# squaresynth.net
KiCad netlist of a schematic drawn in EAGLE
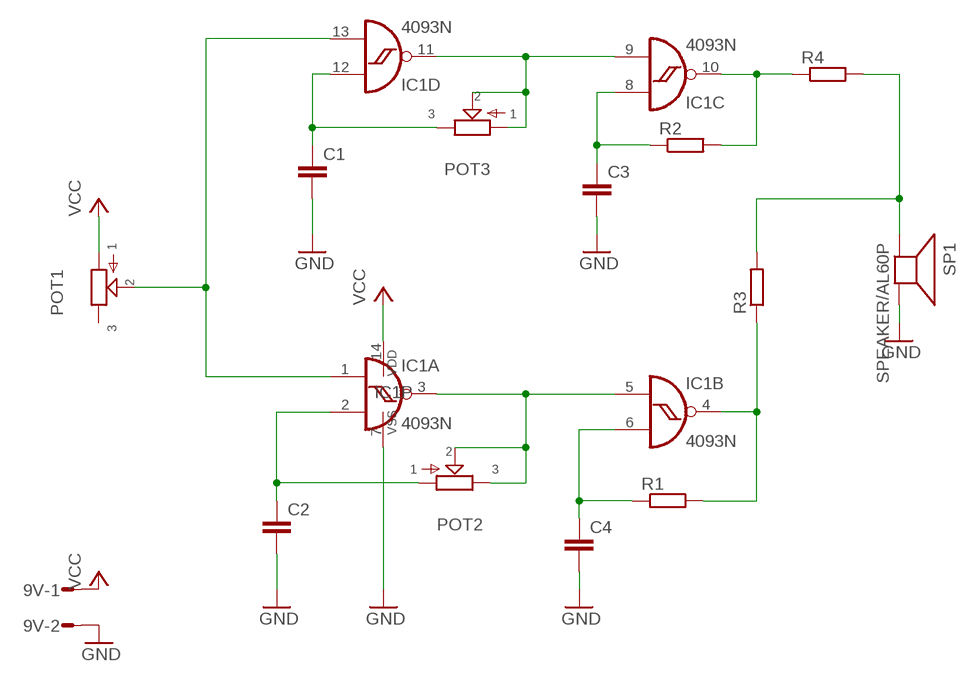
[diagram p0: schematic, sheet 1]

(export (version "E")
  (design (tool "Eeschema 10.0.6"))
  (components
    (comp (ref "9V")
      (value "M02S")
      (footprint "eagle-import:02P")
      (libsource (lib "eagle-import") (part "M02S"))
    )
    (comp (ref "C1")
      (value "C-EU050-030X075")
      (footprint "eagle-import:C050-030X075")
      (libsource (lib "eagle-import") (part "C-EU050-030X075"))
    )
    (comp (ref "C2")
      (value "C-EU050-030X075")
      (footprint "eagle-import:C050-030X075")
      (libsource (lib "eagle-import") (part "C-EU050-030X075"))
    )
    (comp (ref "C3")
      (value "C-EU075-032X103")
      (footprint "eagle-import:C075-032X103")
      (libsource (lib "eagle-import") (part "C-EU075-032X103"))
    )
    (comp (ref "C4")
      (value "C-EU075-032X103")
      (footprint "eagle-import:C075-032X103")
      (libsource (lib "eagle-import") (part "C-EU075-032X103"))
    )
    (comp (ref "IC1")
      (value "4093N")
      (footprint "eagle-import:DIL14")
      (libsource (lib "eagle-import") (part "4093N"))
    )
    (comp (ref "POT1")
      (value "POT-EU16MM")
      (footprint "eagle-import:16MM")
      (libsource (lib "eagle-import") (part "POT-EU16MM"))
    )
    (comp (ref "POT2")
      (value "POT-EU16MM")
      (footprint "eagle-import:16MM")
      (libsource (lib "eagle-import") (part "POT-EU16MM"))
    )
    (comp (ref "POT3")
      (value "POT-EU16MM")
      (footprint "eagle-import:16MM")
      (libsource (lib "eagle-import") (part "POT-EU16MM"))
    )
    (comp (ref "R1")
      (value "R-EU_0309/12")
      (footprint "eagle-import:0309_12")
      (libsource (lib "eagle-import") (part "R-EU_0309/12"))
    )
    (comp (ref "R2")
      (value "R-EU_0309/12")
      (footprint "eagle-import:0309_12")
      (libsource (lib "eagle-import") (part "R-EU_0309/12"))
    )
    (comp (ref "R3")
      (value "R-EU_0309/12")
      (footprint "eagle-import:0309_12")
      (libsource (lib "eagle-import") (part "R-EU_0309/12"))
    )
    (comp (ref "R4")
      (value "R-EU_0309/12")
      (footprint "eagle-import:0309_12")
      (libsource (lib "eagle-import") (part "R-EU_0309/12"))
    )
    (comp (ref "SP1")
      (value "SPEAKER/AL60P")
      (footprint "eagle-import:AL60P")
      (libsource (lib "eagle-import") (part "SPEAKER/AL60P"))
    )
  )
  (nets
    (net (code "1") (name "GND") (class "Default")
      (node (ref "9V") (pin "2") (pinfunction "S_2") (pintype "passive"))
      (node (ref "C1") (pin "2") (pinfunction "2_2") (pintype "passive"))
      (node (ref "C2") (pin "2") (pinfunction "2_2") (pintype "passive"))
      (node (ref "C3") (pin "2") (pinfunction "2_2") (pintype "passive"))
      (node (ref "C4") (pin "2") (pinfunction "2_2") (pintype "passive"))
      (node (ref "IC1") (pin "7") (pinfunction "VSS_7") (pintype "power_in"))
      (node (ref "SP1") (pin "2") (pinfunction "-_2") (pintype "passive"))
    )
    (net (code "2") (name "Net-(IC1A-I0)") (class "Default")
      (node (ref "IC1") (pin "1") (pinfunction "I0_1") (pintype "input"))
      (node (ref "IC1") (pin "13") (pinfunction "I1_13") (pintype "input"))
      (node (ref "POT1") (pin "2") (pinfunction "2_2") (pintype "passive"))
    )
    (net (code "3") (name "Net-(IC1A-I1)") (class "Default")
      (node (ref "C2") (pin "1") (pinfunction "1_1") (pintype "passive"))
      (node (ref "IC1") (pin "2") (pinfunction "I1_2") (pintype "input"))
      (node (ref "POT2") (pin "1") (pinfunction "1_1") (pintype "passive"))
    )
    (net (code "4") (name "Net-(IC1A-O)") (class "Default")
      (node (ref "IC1") (pin "3") (pinfunction "O_3") (pintype "output"))
      (node (ref "IC1") (pin "5") (pinfunction "I0_5") (pintype "input"))
      (node (ref "POT2") (pin "2") (pinfunction "2_2") (pintype "passive"))
      (node (ref "POT2") (pin "3") (pinfunction "3_3") (pintype "passive"))
    )
    (net (code "5") (name "Net-(IC1B-I1)") (class "Default")
      (node (ref "C4") (pin "1") (pinfunction "1_1") (pintype "passive"))
      (node (ref "IC1") (pin "6") (pinfunction "I1_6") (pintype "input"))
      (node (ref "R1") (pin "1") (pinfunction "1_1") (pintype "passive"))
    )
    (net (code "6") (name "Net-(IC1B-O)") (class "Default")
      (node (ref "IC1") (pin "4") (pinfunction "O_4") (pintype "output"))
      (node (ref "R1") (pin "2") (pinfunction "2_2") (pintype "passive"))
      (node (ref "R3") (pin "1") (pinfunction "1_1") (pintype "passive"))
    )
    (net (code "7") (name "Net-(IC1C-I0)") (class "Default")
      (node (ref "C3") (pin "1") (pinfunction "1_1") (pintype "passive"))
      (node (ref "IC1") (pin "8") (pinfunction "I0_8") (pintype "input"))
      (node (ref "R2") (pin "1") (pinfunction "1_1") (pintype "passive"))
    )
    (net (code "8") (name "Net-(IC1C-I1)") (class "Default")
      (node (ref "IC1") (pin "11") (pinfunction "O_11") (pintype "output"))
      (node (ref "IC1") (pin "9") (pinfunction "I1_9") (pintype "input"))
      (node (ref "POT3") (pin "1") (pinfunction "1_1") (pintype "passive"))
      (node (ref "POT3") (pin "2") (pinfunction "2_2") (pintype "passive"))
    )
    (net (code "9") (name "Net-(IC1C-O)") (class "Default")
      (node (ref "IC1") (pin "10") (pinfunction "O_10") (pintype "output"))
      (node (ref "R2") (pin "2") (pinfunction "2_2") (pintype "passive"))
      (node (ref "R4") (pin "1") (pinfunction "1_1") (pintype "passive"))
    )
    (net (code "10") (name "Net-(IC1D-I0)") (class "Default")
      (node (ref "C1") (pin "1") (pinfunction "1_1") (pintype "passive"))
      (node (ref "IC1") (pin "12") (pinfunction "I0_12") (pintype "input"))
      (node (ref "POT3") (pin "3") (pinfunction "3_3") (pintype "passive"))
    )
    (net (code "11") (name "Net-(SP1-+)") (class "Default")
      (node (ref "R3") (pin "2") (pinfunction "2_2") (pintype "passive"))
      (node (ref "R4") (pin "2") (pinfunction "2_2") (pintype "passive"))
      (node (ref "SP1") (pin "1") (pinfunction "+_1") (pintype "passive"))
    )
    (net (code "12") (name "VCC") (class "Default")
      (node (ref "9V") (pin "1") (pinfunction "S_1") (pintype "passive"))
      (node (ref "IC1") (pin "14") (pinfunction "VDD_14") (pintype "power_in"))
      (node (ref "POT1") (pin "1") (pinfunction "1_1") (pintype "passive"))
    )
    (net (code "13") (name "unconnected-(POT1-Pad3)") (class "Default")
      (node (ref "POT1") (pin "3") (pinfunction "3_3") (pintype "passive"))
    )
  )
)
